# rpisupply.net
KiCad netlist of a schematic drawn in EAGLE
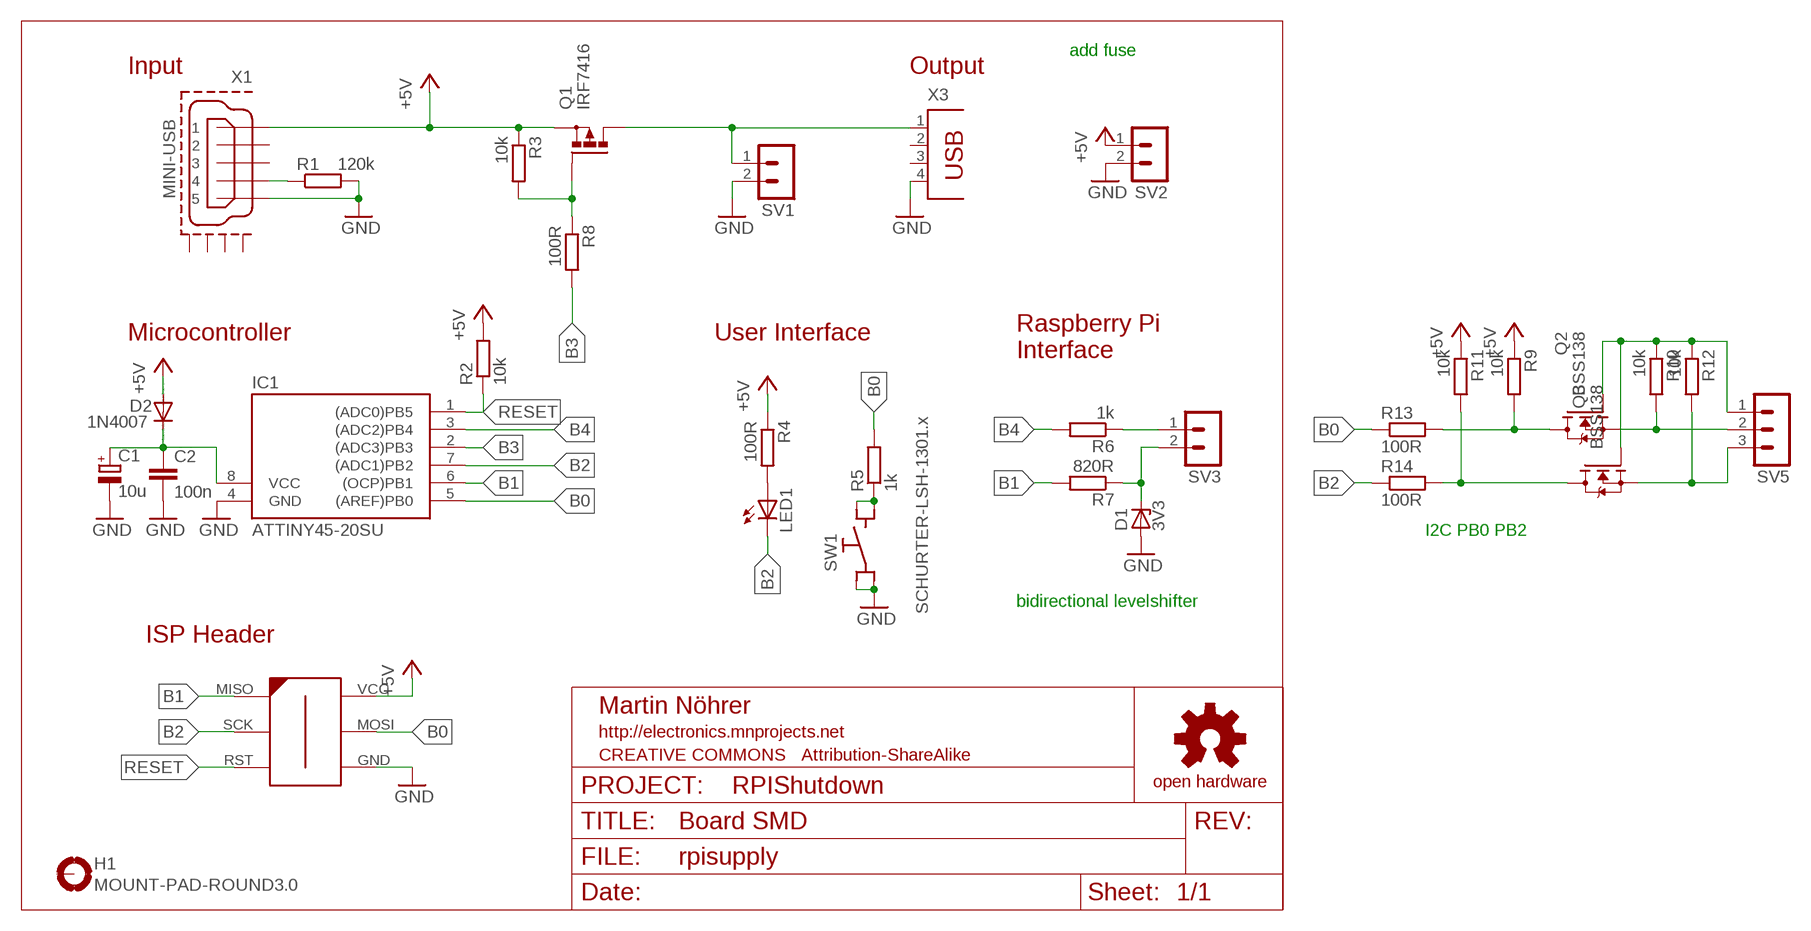
[diagram p0: schematic, sheet 1]

(export (version "E")
  (design (tool "Eeschema 10.0.6"))
  (components
    (comp (ref "C1")
      (value "10u")
      (footprint "eagle-import:SMC_C")
      (libsource (lib "eagle-import") (part "CPOL-EUSMCC"))
    )
    (comp (ref "C2")
      (value "100n")
      (footprint "eagle-import:C0805")
      (libsource (lib "eagle-import") (part "C-EUC0805"))
    )
    (comp (ref "D1")
      (value "3V3")
      (footprint "eagle-import:SOD80C")
      (libsource (lib "eagle-import") (part "ZENER-DIODESOD80C"))
    )
    (comp (ref "D2")
      (value "1N4007")
      (footprint "eagle-import:MELF-MLL41")
      (libsource (lib "eagle-import") (part "DIODE-MELF-MLL41"))
    )
    (comp (ref "H1")
      (value "MOUNT-PAD-ROUND3.0")
      (footprint "eagle-import:3,0-PAD")
      (libsource (lib "eagle-import") (part "MOUNT-PAD-ROUND3.0"))
    )
    (comp (ref "IC1")
      (value "ATTINY45-20SU")
      (footprint "eagle-import:SOIC8")
      (libsource (lib "eagle-import") (part "TINY25/45/85-20SU"))
    )
    (comp (ref "LED1")
      (value "LEDSML0805")
      (footprint "eagle-import:SML0805")
      (libsource (lib "eagle-import") (part "LEDSML0805"))
    )
    (comp (ref "Q1")
      (value "IRF7416")
      (footprint "eagle-import:SO-08")
      (libsource (lib "eagle-import") (part "P-MOSFET-SO8"))
    )
    (comp (ref "Q2")
      (value "BSS138")
      (footprint "eagle-import:SOT23")
      (libsource (lib "eagle-import") (part "BSS138BSS138"))
    )
    (comp (ref "Q3")
      (value "BSS138")
      (footprint "eagle-import:SOT23")
      (libsource (lib "eagle-import") (part "BSS138BSS138"))
    )
    (comp (ref "R1")
      (value "120k")
      (footprint "eagle-import:R0805")
      (libsource (lib "eagle-import") (part "R-EU_R0805"))
    )
    (comp (ref "R2")
      (value "10k")
      (footprint "eagle-import:R0805")
      (libsource (lib "eagle-import") (part "R-EU_R0805"))
    )
    (comp (ref "R3")
      (value "10k")
      (footprint "eagle-import:R0805")
      (libsource (lib "eagle-import") (part "R-EU_R0805"))
    )
    (comp (ref "R4")
      (value "100R")
      (footprint "eagle-import:R0805")
      (libsource (lib "eagle-import") (part "R-EU_R0805"))
    )
    (comp (ref "R5")
      (value "1k")
      (footprint "eagle-import:R0805")
      (libsource (lib "eagle-import") (part "R-EU_R0805"))
    )
    (comp (ref "R6")
      (value "1k")
      (footprint "eagle-import:R0805")
      (libsource (lib "eagle-import") (part "R-EU_R0805"))
    )
    (comp (ref "R7")
      (value "820R")
      (footprint "eagle-import:R0805")
      (libsource (lib "eagle-import") (part "R-EU_R0805"))
    )
    (comp (ref "R8")
      (value "100R")
      (footprint "eagle-import:R0805")
      (libsource (lib "eagle-import") (part "R-EU_R0805"))
    )
    (comp (ref "R9")
      (value "10k")
      (footprint "eagle-import:R0805")
      (libsource (lib "eagle-import") (part "R-EU_R0805"))
    )
    (comp (ref "R10")
      (value "10k")
      (footprint "eagle-import:R0805")
      (libsource (lib "eagle-import") (part "R-EU_R0805"))
    )
    (comp (ref "R11")
      (value "10k")
      (footprint "eagle-import:R0805")
      (libsource (lib "eagle-import") (part "R-EU_R0805"))
    )
    (comp (ref "R12")
      (value "10k")
      (footprint "eagle-import:R0805")
      (libsource (lib "eagle-import") (part "R-EU_R0805"))
    )
    (comp (ref "R13")
      (value "100R")
      (footprint "eagle-import:R0805")
      (libsource (lib "eagle-import") (part "R-EU_R0805"))
    )
    (comp (ref "R14")
      (value "100R")
      (footprint "eagle-import:R0805")
      (libsource (lib "eagle-import") (part "R-EU_R0805"))
    )
    (comp (ref "SV1")
      (value "MA02-1R")
      (footprint "eagle-import:MA02-1")
      (libsource (lib "eagle-import") (part "MA02-1R"))
    )
    (comp (ref "SV2")
      (value "MA02-1R")
      (footprint "eagle-import:MA02-1")
      (libsource (lib "eagle-import") (part "MA02-1R"))
    )
    (comp (ref "SV3")
      (value "MA02-1R")
      (footprint "eagle-import:MA02-1")
      (libsource (lib "eagle-import") (part "MA02-1R"))
    )
    (comp (ref "SV5")
      (value "MA03-1R")
      (footprint "eagle-import:MA03-1")
      (libsource (lib "eagle-import") (part "MA03-1R"))
    )
    (comp (ref "SW1")
      (value "SCHURTER-LSH-1301.x")
      (footprint "eagle-import:LSH")
      (libsource (lib "eagle-import") (part "SCHURTER-LSH-1301.9319"))
    )
    (comp (ref "X1")
      (value "MINI-USB")
      (footprint "eagle-import:UX60-MB-5ST")
      (libsource (lib "eagle-import") (part "MINI-USB-SHIELD-UX60-MB-5ST"))
    )
    (comp (ref "X2")
      (value "AVR-ISP-6-EDGE")
      (footprint "eagle-import:6PAD_ISP")
      (libsource (lib "eagle-import") (part "AVR-ISP-6-EDGE"))
    )
    (comp (ref "X3")
      (value "PN87520")
      (footprint "eagle-import:PN87520")
      (libsource (lib "eagle-import") (part "PN87520"))
    )
  )
  (nets
    (net (code "1") (name "+5V") (class "Default")
      (node (ref "D2") (pin "A") (pinfunction "A_A") (pintype "passive"))
      (node (ref "Q1") (pin "1") (pinfunction "S_1") (pintype "passive"))
      (node (ref "Q1") (pin "2") (pinfunction "S_2") (pintype "passive"))
      (node (ref "Q1") (pin "3") (pinfunction "S_3") (pintype "passive"))
      (node (ref "R11") (pin "1") (pinfunction "1_1") (pintype "passive"))
      (node (ref "R2") (pin "2") (pinfunction "2_2") (pintype "passive"))
      (node (ref "R3") (pin "1") (pinfunction "1_1") (pintype "passive"))
      (node (ref "R4") (pin "1") (pinfunction "1_1") (pintype "passive"))
      (node (ref "R9") (pin "1") (pinfunction "1_1") (pintype "passive"))
      (node (ref "SV2") (pin "1") (pinfunction "1_1") (pintype "passive"))
      (node (ref "X1") (pin "1") (pinfunction "1_1") (pintype "input"))
      (node (ref "X2") (pin "VCC") (pinfunction "P$6_VCC") (pintype "bidirectional"))
    )
    (net (code "2") (name "B0") (class "Default")
      (node (ref "IC1") (pin "5") (pinfunction "(AREF)PB0_5") (pintype "bidirectional"))
      (node (ref "R13") (pin "1") (pinfunction "1_1") (pintype "passive"))
      (node (ref "R5") (pin "2") (pinfunction "2_2") (pintype "passive"))
      (node (ref "X2") (pin "MOSI") (pinfunction "P$5_MOSI") (pintype "bidirectional"))
    )
    (net (code "3") (name "B1") (class "Default")
      (node (ref "IC1") (pin "6") (pinfunction "(OCP)PB1_6") (pintype "bidirectional"))
      (node (ref "R7") (pin "2") (pinfunction "2_2") (pintype "passive"))
      (node (ref "X2") (pin "MISO") (pinfunction "P$1_MISO") (pintype "bidirectional"))
    )
    (net (code "4") (name "B2") (class "Default")
      (node (ref "IC1") (pin "7") (pinfunction "(ADC1)PB2_7") (pintype "bidirectional"))
      (node (ref "LED1") (pin "C") (pinfunction "C_C") (pintype "passive"))
      (node (ref "R14") (pin "1") (pinfunction "1_1") (pintype "passive"))
      (node (ref "X2") (pin "SCK") (pinfunction "P$2_SCK") (pintype "bidirectional"))
    )
    (net (code "5") (name "B3") (class "Default")
      (node (ref "IC1") (pin "2") (pinfunction "(ADC3)PB3_2") (pintype "bidirectional"))
      (node (ref "R8") (pin "2") (pinfunction "2_2") (pintype "passive"))
    )
    (net (code "6") (name "B4") (class "Default")
      (node (ref "IC1") (pin "3") (pinfunction "(ADC2)PB4_3") (pintype "bidirectional"))
      (node (ref "R6") (pin "2") (pinfunction "2_2") (pintype "passive"))
    )
    (net (code "7") (name "GND") (class "Default")
      (node (ref "C1") (pin "-") (pinfunction "-_-") (pintype "passive"))
      (node (ref "C2") (pin "2") (pinfunction "2_2") (pintype "passive"))
      (node (ref "D1") (pin "A") (pinfunction "A_A") (pintype "passive"))
      (node (ref "IC1") (pin "4") (pinfunction "GND_4") (pintype "power_in"))
      (node (ref "R1") (pin "2") (pinfunction "2_2") (pintype "passive"))
      (node (ref "SV1") (pin "2") (pinfunction "2_2") (pintype "passive"))
      (node (ref "SV2") (pin "2") (pinfunction "2_2") (pintype "passive"))
      (node (ref "SW1") (pin "C1") (pinfunction "C_C1") (pintype "passive"))
      (node (ref "SW1") (pin "C2") (pinfunction "C_C2") (pintype "passive"))
      (node (ref "X1") (pin "5") (pinfunction "5_5") (pintype "input"))
      (node (ref "X2") (pin "GND") (pinfunction "P$4_GND") (pintype "bidirectional"))
      (node (ref "X3") (pin "4") (pinfunction "4_4") (pintype "passive"))
    )
    (net (code "8") (name "Net-(D1-PadC)") (class "Default")
      (node (ref "D1") (pin "C") (pinfunction "C_C") (pintype "passive"))
      (node (ref "R7") (pin "1") (pinfunction "1_1") (pintype "passive"))
      (node (ref "SV3") (pin "2") (pinfunction "2_2") (pintype "passive"))
    )
    (net (code "9") (name "Net-(IC1-VCC)") (class "Default")
      (node (ref "C1") (pin "+") (pinfunction "+_+") (pintype "passive"))
      (node (ref "C2") (pin "1") (pinfunction "1_1") (pintype "passive"))
      (node (ref "D2") (pin "C") (pinfunction "C_C") (pintype "passive"))
      (node (ref "IC1") (pin "8") (pinfunction "VCC_8") (pintype "power_in"))
    )
    (net (code "10") (name "Net-(LED1-PadA)") (class "Default")
      (node (ref "LED1") (pin "A") (pinfunction "A_A") (pintype "passive"))
      (node (ref "R4") (pin "2") (pinfunction "2_2") (pintype "passive"))
    )
    (net (code "11") (name "Net-(Q1-D-Pad5)") (class "Default")
      (node (ref "Q1") (pin "5") (pinfunction "D_5") (pintype "passive"))
      (node (ref "Q1") (pin "6") (pinfunction "D_6") (pintype "passive"))
      (node (ref "Q1") (pin "7") (pinfunction "D_7") (pintype "passive"))
      (node (ref "Q1") (pin "8") (pinfunction "D_8") (pintype "passive"))
      (node (ref "SV1") (pin "1") (pinfunction "1_1") (pintype "passive"))
      (node (ref "X3") (pin "1") (pinfunction "1_1") (pintype "passive"))
    )
    (net (code "12") (name "Net-(Q1-G)") (class "Default")
      (node (ref "Q1") (pin "4") (pinfunction "G_4") (pintype "passive"))
      (node (ref "R3") (pin "2") (pinfunction "2_2") (pintype "passive"))
      (node (ref "R8") (pin "1") (pinfunction "1_1") (pintype "passive"))
    )
    (net (code "13") (name "Net-(Q2-D)") (class "Default")
      (node (ref "Q2") (pin "3") (pinfunction "D_3") (pintype "passive"))
      (node (ref "R13") (pin "2") (pinfunction "2_2") (pintype "passive"))
      (node (ref "R9") (pin "2") (pinfunction "2_2") (pintype "passive"))
    )
    (net (code "14") (name "Net-(Q2-G)") (class "Default")
      (node (ref "Q2") (pin "1") (pinfunction "G_1") (pintype "passive"))
      (node (ref "Q3") (pin "1") (pinfunction "G_1") (pintype "passive"))
      (node (ref "R10") (pin "1") (pinfunction "1_1") (pintype "passive"))
      (node (ref "R12") (pin "1") (pinfunction "1_1") (pintype "passive"))
      (node (ref "SV5") (pin "1") (pinfunction "1_1") (pintype "passive"))
    )
    (net (code "15") (name "Net-(Q2-S)") (class "Default")
      (node (ref "Q2") (pin "2") (pinfunction "S_2") (pintype "passive"))
      (node (ref "R10") (pin "2") (pinfunction "2_2") (pintype "passive"))
      (node (ref "SV5") (pin "2") (pinfunction "2_2") (pintype "passive"))
    )
    (net (code "16") (name "Net-(Q3-D)") (class "Default")
      (node (ref "Q3") (pin "3") (pinfunction "D_3") (pintype "passive"))
      (node (ref "R11") (pin "2") (pinfunction "2_2") (pintype "passive"))
      (node (ref "R14") (pin "2") (pinfunction "2_2") (pintype "passive"))
    )
    (net (code "17") (name "Net-(Q3-S)") (class "Default")
      (node (ref "Q3") (pin "2") (pinfunction "S_2") (pintype "passive"))
      (node (ref "R12") (pin "2") (pinfunction "2_2") (pintype "passive"))
      (node (ref "SV5") (pin "3") (pinfunction "3_3") (pintype "passive"))
    )
    (net (code "18") (name "Net-(R1-Pad1)") (class "Default")
      (node (ref "R1") (pin "1") (pinfunction "1_1") (pintype "passive"))
      (node (ref "X1") (pin "4") (pinfunction "4_4") (pintype "input"))
    )
    (net (code "19") (name "Net-(R5-Pad1)") (class "Default")
      (node (ref "R5") (pin "1") (pinfunction "1_1") (pintype "passive"))
      (node (ref "SW1") (pin "NO1") (pinfunction "NO_NO1") (pintype "passive"))
      (node (ref "SW1") (pin "NO2") (pinfunction "NO_NO2") (pintype "passive"))
    )
    (net (code "20") (name "Net-(R6-Pad1)") (class "Default")
      (node (ref "R6") (pin "1") (pinfunction "1_1") (pintype "passive"))
      (node (ref "SV3") (pin "1") (pinfunction "1_1") (pintype "passive"))
    )
    (net (code "21") (name "RESET") (class "Default")
      (node (ref "IC1") (pin "1") (pinfunction "(ADC0)PB5_1") (pintype "bidirectional"))
      (node (ref "R2") (pin "1") (pinfunction "1_1") (pintype "passive"))
      (node (ref "X2") (pin "RST") (pinfunction "P$3_RST") (pintype "bidirectional"))
    )
    (net (code "22") (name "unconnected-(H1-MOUNT-PadB3,0)") (class "Default")
      (node (ref "H1") (pin "B3,0") (pinfunction "MOUNT_B3,0") (pintype "passive"))
    )
    (net (code "23") (name "unconnected-(X1-GND1-PadM1)") (class "Default")
      (node (ref "X1") (pin "M1") (pinfunction "GND1_M1") (pintype "bidirectional"))
    )
    (net (code "24") (name "unconnected-(X1-GND2-PadM2)") (class "Default")
      (node (ref "X1") (pin "M2") (pinfunction "GND2_M2") (pintype "bidirectional"))
    )
    (net (code "25") (name "unconnected-(X1-GND3-PadM3)") (class "Default")
      (node (ref "X1") (pin "M3") (pinfunction "GND3_M3") (pintype "bidirectional"))
    )
    (net (code "26") (name "unconnected-(X1-GND4-PadM4)") (class "Default")
      (node (ref "X1") (pin "M4") (pinfunction "GND4_M4") (pintype "bidirectional"))
    )
    (net (code "27") (name "unconnected-(X1-Pad2)") (class "Default")
      (node (ref "X1") (pin "2") (pinfunction "2_2") (pintype "input"))
    )
    (net (code "28") (name "unconnected-(X1-Pad3)") (class "Default")
      (node (ref "X1") (pin "3") (pinfunction "3_3") (pintype "input"))
    )
    (net (code "29") (name "unconnected-(X3-Pad2)") (class "Default")
      (node (ref "X3") (pin "2") (pinfunction "2_2") (pintype "passive"))
    )
    (net (code "30") (name "unconnected-(X3-Pad3)") (class "Default")
      (node (ref "X3") (pin "3") (pinfunction "3_3") (pintype "passive"))
    )
  )
)
